# 04_POWER_SUPPLY.net
KiCad netlist of a schematic drawn in Altium Designer
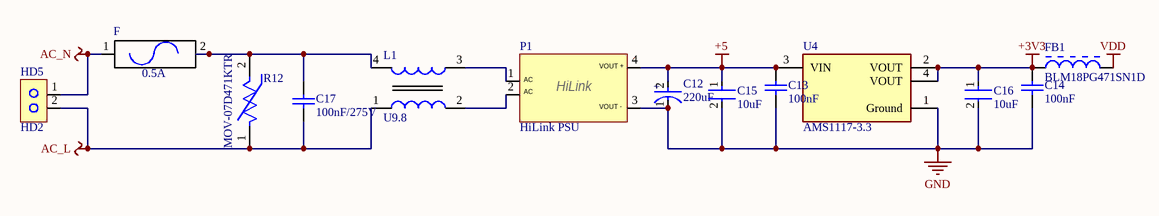
[diagram p0: 04. POWER SUPPLY.SchDoc]

(export (version "E")
  (design (tool "Eeschema 10.0.6"))
  (components
    (comp (ref "C12")
      (value "220uF")
      (footprint "FP-ESTG4-MFG")
      (description "CAP ALUM 220UF 20% 35V RADIAL")
      (fields
        (field (name "OCTOPART") "https://octopart.com/est227m035ag4aa-kemet-22264647")
        (field (name "MANUFACTURER PART NUMBER") "EST227M035AG4AA")
      )
      (libsource (lib "Altium Content Vault") (part "a00bbbee19879c290e62620ae7e47b1"))
    )
    (comp (ref "C13")
      (value "100nF")
      (footprint "0603 CAP")
      (description "Chip Capacitor, 0.1 uF, +/- 10%, 50 V, -55 to 125 degC, 0603 (1608 Metric), RoHS, Tape and Reel")
      (fields (field (name "TOLERANCE") "10%") (field (name "VOLTAGE") "50V"))
      (libsource (lib "SyTungNguyen") (part "CAP-NP-2"))
    )
    (comp (ref "C14")
      (value "100nF")
      (footprint "0603 CAP")
      (description "Chip Capacitor, 0.1 uF, +/- 10%, 50 V, -55 to 125 degC, 0603 (1608 Metric), RoHS, Tape and Reel")
      (fields (field (name "TOLERANCE") "10%") (field (name "VOLTAGE") "50V"))
      (libsource (lib "SyTungNguyen") (part "CAP-NP-2"))
    )
    (comp (ref "C15")
      (value "10uF")
      (footprint "FP-CGA5L-0_3-0_1-IPC_B")
      (description "Cap Ceramic 10uF 25V X7R 10% Pad SMD 1206 +125°C Automotive T/R")
      (fields (field (name "TOLERANCE") "10%"))
      (libsource (lib "Altium Content Vault") (part "b4654b650e69147ec39a6b967a45e02"))
    )
    (comp (ref "C16")
      (value "10uF")
      (footprint "FP-CGA5L-0_3-0_1-IPC_B")
      (description "Cap Ceramic 10uF 25V X7R 10% Pad SMD 1206 +125°C Automotive T/R")
      (fields (field (name "TOLERANCE") "10%"))
      (libsource (lib "Altium Content Vault") (part "b4654b650e69147ec39a6b967a45e02"))
    )
    (comp (ref "C17")
      (value "100nF/275V")
      (footprint "CAP 12.5mm Pitch")
      (description "Chip Capacitor, 0.1 uF, +/- 10%, 400 V, -55 to 125 degC, 0603 (1608 Metric), RoHS, Tape and Reel")
      (fields (field (name "TOLERANCE") "10%") (field (name "VOLTAGE") "50V"))
      (libsource (lib "SyTungNguyen") (part "CAP-NP-2"))
    )
    (comp (ref "F") (value "0.5A") (footprint "FUSE 20mm") (libsource (lib "SyTungNguyen") (part "FUSE")))
    (comp (ref "FB1")
      (value "BLM18PG471SN1D")
      (footprint "0603 Ferrite")
      (fields (field (name "MANUFACTURER") "Murata"))
      (libsource (lib "SyTungNguyen") (part "MURA-FB-2"))
    )
    (comp (ref "HD5") (value "HD2") (footprint "HD2 5.08mm") (libsource (lib "SyTungNguyen") (part "HD2")))
    (comp (ref "L1")
      (value "U9.8")
      (footprint "INDUCTOR FILTER U9.8")
      (libsource (lib "SyTungNguyen") (part "INDUCTOR FILTER"))
    )
    (comp (ref "P1")
      (value "HiLink PSU")
      (footprint "HLK-5M05")
      (libsource (lib "SyTungNguyen") (part "HiLink PSU"))
    )
    (comp (ref "R12")
      (value "MOV-07D471KTR")
      (footprint "FP-MOV-07D471KTR-MFG")
      (description "VARISTOR 470V 1.2KA DISC 7MM")
      (fields
        (field (name "OCTOPART") "https://octopart.com/mov-07d471ktr-bourns-19184728")
        (field (name "MANUFACTURER") "Bourns Inc.")
      )
      (libsource (lib "Altium Content Vault") (part "78a88060d5b7b043d6e48adc4284376"))
    )
    (comp (ref "U4")
      (value "AMS1117-3.3")
      (footprint "FP-AMS1117-IPC_C")
      (description "LDO Voltage Regulators 1A, 3.3V")
      (fields
        (field (name "OCTOPART") "https://octopart.com/ams1117-3.3-advanced+monolithic+systems-25899300")
        (field (name "MANUFACTURER") "Advanced Monolithic Systems")
      )
      (libsource (lib "Altium Content Vault") (part "8bdbb5f8e77002000e30dd2845d0354"))
    )
  )
  (nets
    (net (code "1") (name "+3V3") (class "Default")
      (node (ref "C14") (pin "2") (pinfunction "2_2") (pintype "passive"))
      (node (ref "C16") (pin "1") (pinfunction "1_1") (pintype "passive"))
      (node (ref "FB1") (pin "1") (pinfunction "1_1") (pintype "passive"))
      (node (ref "U4") (pin "2") (pinfunction "VOUT_2") (pintype "passive"))
      (node (ref "U4") (pin "4") (pinfunction "VOUT_4") (pintype "passive"))
    )
    (net (code "2") (name "+5") (class "Default")
      (node (ref "C12") (pin "2") (pinfunction "A_2") (pintype "passive"))
      (node (ref "C13") (pin "2") (pinfunction "2_2") (pintype "passive"))
      (node (ref "C15") (pin "1") (pinfunction "1_1") (pintype "passive"))
      (node (ref "P1") (pin "4") (pinfunction "4_4") (pintype "passive"))
      (node (ref "U4") (pin "3") (pinfunction "VIN_3") (pintype "power_in"))
    )
    (net (code "3") (name "AC_L") (class "Default")
      (node (ref "C17") (pin "1") (pinfunction "1_1") (pintype "passive"))
      (node (ref "HD5") (pin "2") (pinfunction "2_2") (pintype "passive"))
      (node (ref "L1") (pin "1") (pinfunction "1_1") (pintype "passive"))
      (node (ref "R12") (pin "1") (pinfunction "1_1") (pintype "passive"))
    )
    (net (code "4") (name "AC_N") (class "Default")
      (node (ref "F") (pin "1") (pinfunction "1_1") (pintype "passive"))
      (node (ref "HD5") (pin "1") (pinfunction "1_1") (pintype "passive"))
    )
    (net (code "5") (name "GND") (class "Default")
      (node (ref "C12") (pin "1") (pinfunction "C_1") (pintype "passive"))
      (node (ref "C13") (pin "1") (pinfunction "1_1") (pintype "passive"))
      (node (ref "C14") (pin "1") (pinfunction "1_1") (pintype "passive"))
      (node (ref "C15") (pin "2") (pinfunction "2_2") (pintype "passive"))
      (node (ref "C16") (pin "2") (pinfunction "2_2") (pintype "passive"))
      (node (ref "P1") (pin "3") (pinfunction "3_3") (pintype "passive"))
      (node (ref "U4") (pin "1") (pinfunction "Ground_1") (pintype "power_in"))
    )
    (net (code "6") (name "Net-(C17-Pad2)") (class "Default")
      (node (ref "C17") (pin "2") (pinfunction "2_2") (pintype "passive"))
      (node (ref "F") (pin "2") (pinfunction "2_2") (pintype "passive"))
      (node (ref "L1") (pin "4") (pinfunction "4_4") (pintype "passive"))
      (node (ref "R12") (pin "2") (pinfunction "2_2") (pintype "passive"))
    )
    (net (code "7") (name "Net-(L1-Pad2)") (class "Default")
      (node (ref "L1") (pin "2") (pinfunction "2_2") (pintype "passive"))
      (node (ref "P1") (pin "2") (pinfunction "2_2") (pintype "passive"))
    )
    (net (code "8") (name "Net-(L1-Pad3)") (class "Default")
      (node (ref "L1") (pin "3") (pinfunction "3_3") (pintype "passive"))
      (node (ref "P1") (pin "1") (pinfunction "1_1") (pintype "passive"))
    )
    (net (code "9") (name "VDD") (class "Default")
      (node (ref "FB1") (pin "2") (pinfunction "2_2") (pintype "passive"))
    )
  )
)
